# amplifier.net
KiCad netlist of a schematic drawn in Altium Designer
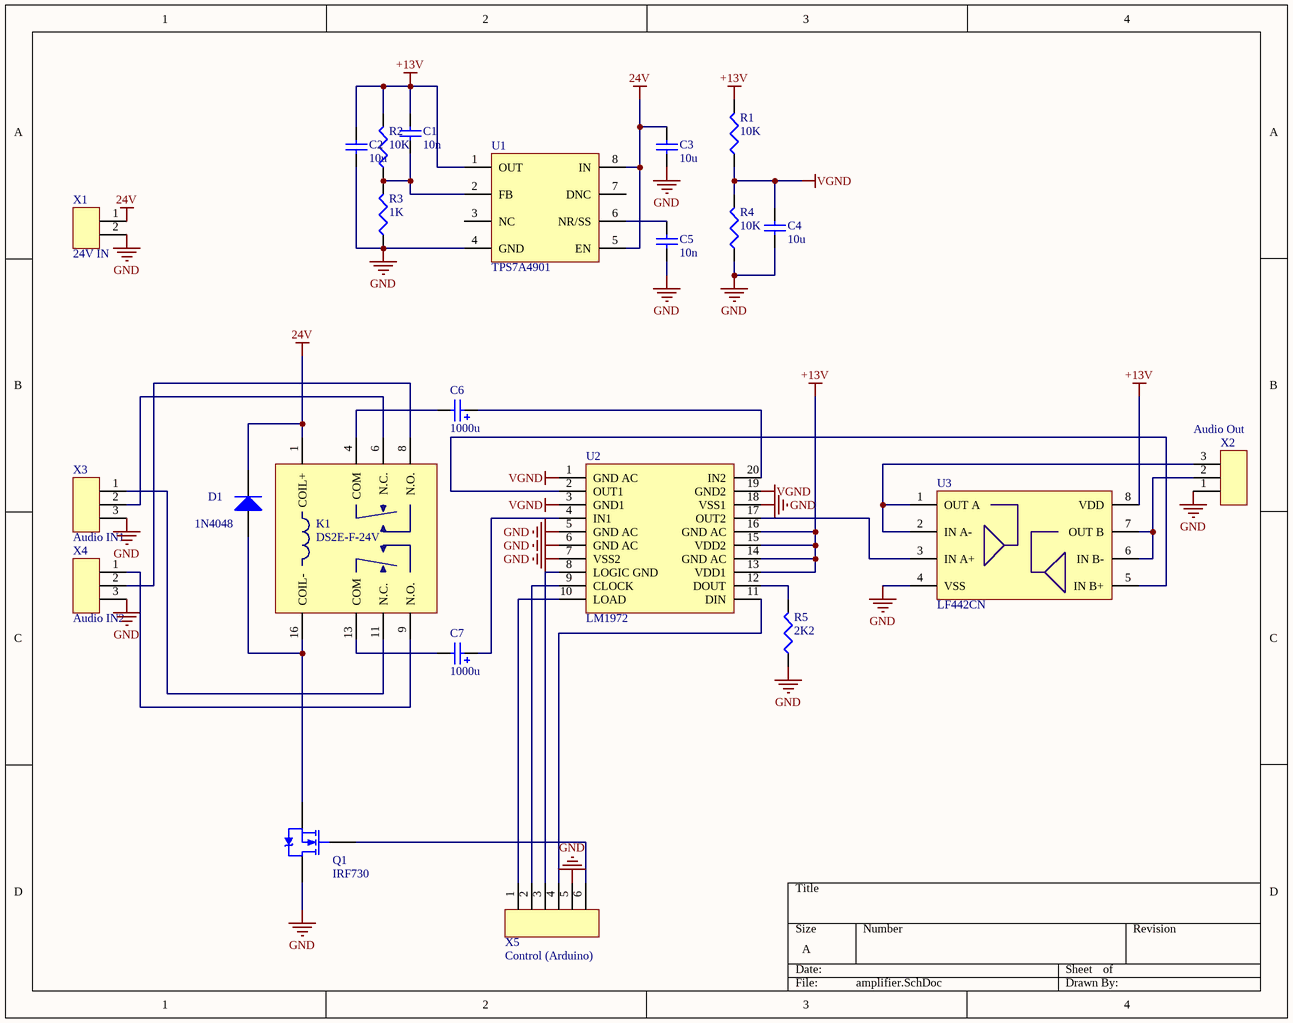
[diagram p0: amplifier.SchDoc]

(export (version "E")
  (design (tool "Eeschema 10.0.6"))
  (components
    (comp (ref "C1")
      (value "10n")
      (footprint "CAPC3216X17N")
      (description "CAP CER 10NF 50V 10% X7R 1206")
      (fields
        (field (name "MANUFACTURER") "Yageo")
        (field (name "MANUFACTURER PART NUMBER") "CC1206KRX7R9BB103")
      )
      (libsource (lib "BaseLab") (part "C1206C103K"))
    )
    (comp (ref "C2")
      (value "10u")
      (footprint "CAPC3216X17N")
      (description "CAP CER 100NF 50V 10% X7R 1206")
      (fields
        (field (name "MANUFACTURER") "Kemet")
        (field (name "MANUFACTURER PART NUMBER") "C1206C104K5RACTU")
      )
      (libsource (lib "BaseLab") (part "C1206C104K"))
    )
    (comp (ref "C3")
      (value "10u")
      (footprint "CAPC3216X17N")
      (description "CAP CER 100NF 50V 10% X7R 1206")
      (fields
        (field (name "MANUFACTURER") "Kemet")
        (field (name "MANUFACTURER PART NUMBER") "C1206C104K5RACTU")
      )
      (libsource (lib "BaseLab") (part "C1206C104K"))
    )
    (comp (ref "C4")
      (value "10u")
      (footprint "CAPC3216X17N")
      (description "CAP CER 100NF 50V 10% X7R 1206")
      (fields
        (field (name "MANUFACTURER") "Kemet")
        (field (name "MANUFACTURER PART NUMBER") "C1206C104K5RACTU")
      )
      (libsource (lib "BaseLab") (part "C1206C104K"))
    )
    (comp (ref "C5")
      (value "10n")
      (footprint "CAPC3216X17N")
      (description "CAP CER 10NF 50V 10% X7R 1206")
      (fields
        (field (name "MANUFACTURER") "Yageo")
        (field (name "MANUFACTURER PART NUMBER") "CC1206KRX7R9BB103")
      )
      (libsource (lib "BaseLab") (part "C1206C103K"))
    )
    (comp (ref "C6")
      (value "1000u")
      (footprint "Radial_0254_0381X0900")
      (description "CAP ALUM 1000UF 16V 20% RADIAL")
      (fields
        (field (name "MANUFACTURER") "Panasonic Electronic Components")
        (field (name "MANUFACTURER PART NUMBER") "ECA-1CM102B")
      )
      (libsource (lib "BaseLab") (part "CA-1CM102"))
    )
    (comp (ref "C7")
      (value "1000u")
      (footprint "Radial_0254_0381X0900")
      (description "CAP ALUM 1000UF 16V 20% RADIAL")
      (fields
        (field (name "MANUFACTURER") "Panasonic Electronic Components")
        (field (name "MANUFACTURER PART NUMBER") "ECA-1CM102B")
      )
      (libsource (lib "BaseLab") (part "CA-1CM102"))
    )
    (comp (ref "D1")
      (value "1N4048")
      (footprint "DO-35")
      (description "275 Amp Avg Power Silicon Rectifier Diode")
      (fields (field (name "PUBLISHER") "Altium Limited"))
      (libsource (lib "IR Rectifier - Standard Recovery") (part "1N4048"))
    )
    (comp (ref "K1")
      (value "DS2E-F-24V")
      (footprint "DS2E-F-DC24V")
      (description "Relay 24V")
      (fields
        (field (name "MANUFACTURER") "Panasonic Electric Works")
        (field (name "MANUFACTURER PART NUMBER") "DS2E-S-DC24V")
      )
      (libsource (lib "BaseLab") (part "DS2E-F-DC24V"))
    )
    (comp (ref "Q1")
      (value "IRF730")
      (footprint "TO-220AB")
      (description "HEXFET N-Channel Power MOSFET")
      (fields (field (name "PUBLISHER") "Altium Limited"))
      (libsource (lib "IR Discrete MOSFET - Power") (part "IRF730"))
    )
    (comp (ref "R1")
      (value "10K")
      (footprint "RESC2012X06M")
      (description "RES 10K OHM 1/8W 1% 0805 SMD")
      (fields
        (field (name "MANUFACTURER") "Yageo")
        (field (name "MANUFACTURER PART NUMBER") "RC0805FR-0710KL")
      )
      (libsource (lib "BaseLab") (part "RC0805FR-0710KL"))
    )
    (comp (ref "R2")
      (value "10K")
      (footprint "RESC2012X06M")
      (description "RES 10K OHM 1/8W 1% 0805 SMD")
      (fields
        (field (name "MANUFACTURER") "Yageo")
        (field (name "MANUFACTURER PART NUMBER") "RC0805FR-0710KL")
      )
      (libsource (lib "BaseLab") (part "RC0805FR-0710KL"))
    )
    (comp (ref "R3")
      (value "1K")
      (footprint "RESC3216X07N")
      (description "RES 1.00K OHM 1/4W 1% 1206 SMD")
      (fields
        (field (name "MANUFACTURER") "Yageo")
        (field (name "MANUFACTURER PART NUMBER") "RC1206FR-071KL")
      )
      (libsource (lib "BaseLab") (part "RC1206FR-071KL"))
    )
    (comp (ref "R4")
      (value "10K")
      (footprint "RESC2012X06M")
      (description "RES 10K OHM 1/8W 1% 0805 SMD")
      (fields
        (field (name "MANUFACTURER") "Yageo")
        (field (name "MANUFACTURER PART NUMBER") "RC0805FR-0710KL")
      )
      (libsource (lib "BaseLab") (part "RC0805FR-0710KL"))
    )
    (comp (ref "R5")
      (value "2K2")
      (footprint "RESC2012X06N")
      (description "RES 2.20K OHM 1/8W 1% 0805 SMD")
      (fields
        (field (name "MANUFACTURER") "Yageo")
        (field (name "MANUFACTURER PART NUMBER") "RC0805FR-072K2L")
      )
      (libsource (lib "BaseLab") (part "RC0805FR-072K2L"))
    )
    (comp (ref "U1")
      (value "TPS7A4901")
      (footprint "MSOP-8")
      (description "IC, ADJ LDO REG, 1.2V-33V, 0.15A, MSOP-8")
      (fields
        (field (name "MANUFACTURER") "Texas Instruments")
        (field (name "MANUFACTURER PART NUMBER") "TPS7A4901DGNR")
      )
      (libsource (lib "BaseLab") (part "TPS7A4901"))
    )
    (comp (ref "U2")
      (value "LM1972")
      (footprint "SOIC-20_0127_7.5mm")
      (libsource (lib "BaseLab") (part "LM1972"))
    )
    (comp (ref "U3")
      (value "LF442CN")
      (footprint "DIP-08_0254_0762_0420")
      (description "LF442 Dual Low Power JFET Input Operational Amplifier")
      (fields (field (name "MANUFACTURER") "TEXAS INSTRUMENTS"))
      (libsource (lib "BaseLab") (part "LF442CN"))
    )
    (comp (ref "X1")
      (value "24V IN")
      (footprint "CON_1X02S_0254")
      (description "Stecker 2-Pin")
      (fields
        (field (name "MANUFACTURER") "Sullins Connector Solutions")
        (field (name "MANUFACTURER PART NUMBER") "PREC040SFAN-RC")
      )
      (libsource (lib "BaseLab") (part "HDR1x02"))
    )
    (comp (ref "X2")
      (value "Audio Out")
      (footprint "CON_1X03S_0254")
      (description "Stecker 3-Pin")
      (fields
        (field (name "MANUFACTURER") "Sullins Connector Solutions")
        (field (name "MANUFACTURER PART NUMBER") "PREC040SFAN-RC")
      )
      (libsource (lib "BaseLab") (part "HDR1x03"))
    )
    (comp (ref "X3")
      (value "Audio IN1")
      (footprint "CON_1X03S_0254")
      (description "Stecker 3-Pin")
      (fields
        (field (name "MANUFACTURER") "Sullins Connector Solutions")
        (field (name "MANUFACTURER PART NUMBER") "PREC040SFAN-RC")
      )
      (libsource (lib "") (part "HDR1x03_1"))
    )
    (comp (ref "X4")
      (value "Audio IN2")
      (footprint "CON_1X03S_0254")
      (description "Stecker 3-Pin")
      (fields
        (field (name "MANUFACTURER") "Sullins Connector Solutions")
        (field (name "MANUFACTURER PART NUMBER") "PREC040SFAN-RC")
      )
      (libsource (lib "") (part "HDR1x03_1"))
    )
    (comp (ref "X5")
      (value "Control (Arduino)")
      (footprint "CON_1X06S_0254")
      (description "Stecker 4-Pin")
      (fields
        (field (name "MANUFACTURER") "Sullins Connector Solutions")
        (field (name "MANUFACTURER PART NUMBER") "PREC040SFAN-RC")
      )
      (libsource (lib "BaseLab") (part "HDR1x06"))
    )
  )
  (nets
    (net (code "1") (name "+13V") (class "Default")
      (node (ref "C1") (pin "2") (pinfunction "2_2") (pintype "passive"))
      (node (ref "C2") (pin "2") (pinfunction "2_2") (pintype "passive"))
      (node (ref "R1") (pin "2") (pinfunction "2_2") (pintype "passive"))
      (node (ref "R2") (pin "2") (pinfunction "2_2") (pintype "passive"))
      (node (ref "U1") (pin "1") (pinfunction "OUT_1") (pintype "passive"))
      (node (ref "U2") (pin "13") (pinfunction "VDD1_13") (pintype "passive"))
      (node (ref "U2") (pin "14") (pinfunction "GND_AC_14") (pintype "passive"))
      (node (ref "U2") (pin "15") (pinfunction "VDD2_15") (pintype "passive"))
      (node (ref "U2") (pin "16") (pinfunction "GND_AC_16") (pintype "passive"))
      (node (ref "U3") (pin "8") (pinfunction "VDD_8") (pintype "passive"))
    )
    (net (code "2") (name "24V") (class "Default")
      (node (ref "C3") (pin "2") (pinfunction "2_2") (pintype "passive"))
      (node (ref "D1") (pin "2") (pinfunction "K_2") (pintype "passive"))
      (node (ref "K1") (pin "1") (pinfunction "COIL+_1") (pintype "passive"))
      (node (ref "U1") (pin "5") (pinfunction "EN_5") (pintype "passive"))
      (node (ref "U1") (pin "8") (pinfunction "IN_8") (pintype "passive"))
      (node (ref "X1") (pin "1") (pinfunction "1_1") (pintype "passive"))
    )
    (net (code "3") (name "GND") (class "Default")
      (node (ref "C2") (pin "1") (pinfunction "1_1") (pintype "passive"))
      (node (ref "C3") (pin "1") (pinfunction "1_1") (pintype "passive"))
      (node (ref "C4") (pin "1") (pinfunction "1_1") (pintype "passive"))
      (node (ref "C5") (pin "1") (pinfunction "1_1") (pintype "passive"))
      (node (ref "Q1") (pin "2") (pinfunction "D_2") (pintype "passive"))
      (node (ref "R3") (pin "1") (pinfunction "1_1") (pintype "passive"))
      (node (ref "R4") (pin "1") (pinfunction "1_1") (pintype "passive"))
      (node (ref "R5") (pin "1") (pinfunction "1_1") (pintype "passive"))
      (node (ref "U1") (pin "4") (pinfunction "GND_4") (pintype "passive"))
      (node (ref "U2") (pin "18") (pinfunction "VSS1_18") (pintype "passive"))
      (node (ref "U2") (pin "5") (pinfunction "GND_AC_5") (pintype "passive"))
      (node (ref "U2") (pin "6") (pinfunction "GND_AC_6") (pintype "passive"))
      (node (ref "U2") (pin "7") (pinfunction "VSS2_7") (pintype "passive"))
      (node (ref "U3") (pin "4") (pinfunction "VSS_4") (pintype "passive"))
      (node (ref "X1") (pin "2") (pinfunction "2_2") (pintype "passive"))
      (node (ref "X2") (pin "1") (pinfunction "1_1") (pintype "passive"))
      (node (ref "X3") (pin "3") (pinfunction "3_3") (pintype "passive"))
      (node (ref "X4") (pin "3") (pinfunction "3_3") (pintype "passive"))
      (node (ref "X5") (pin "5") (pinfunction "5_5") (pintype "passive"))
    )
    (net (code "4") (name "Net-(C6-Pad2)") (class "Default")
      (node (ref "C6") (pin "2") (pinfunction "2_2") (pintype "passive"))
      (node (ref "K1") (pin "4") (pinfunction "COM_4") (pintype "passive"))
    )
    (net (code "5") (name "Net-(C7-Pad2)") (class "Default")
      (node (ref "C7") (pin "2") (pinfunction "2_2") (pintype "passive"))
      (node (ref "K1") (pin "13") (pinfunction "COM_13") (pintype "passive"))
    )
    (net (code "6") (name "Net-(D1-A)") (class "Default")
      (node (ref "D1") (pin "1") (pinfunction "A_1") (pintype "passive"))
      (node (ref "K1") (pin "16") (pinfunction "COIL-_16") (pintype "passive"))
      (node (ref "Q1") (pin "3") (pinfunction "S_3") (pintype "passive"))
    )
    (net (code "7") (name "Net-(K1-N.C.-Pad6)") (class "Default")
      (node (ref "K1") (pin "6") (pinfunction "N.C._6") (pintype "passive"))
      (node (ref "X3") (pin "2") (pinfunction "2_2") (pintype "passive"))
    )
    (net (code "8") (name "Net-(K1-N.C.-Pad11)") (class "Default")
      (node (ref "K1") (pin "11") (pinfunction "N.C._11") (pintype "passive"))
      (node (ref "X3") (pin "1") (pinfunction "1_1") (pintype "passive"))
    )
    (net (code "9") (name "Net-(K1-N.O.-Pad8)") (class "Default")
      (node (ref "K1") (pin "8") (pinfunction "N.O._8") (pintype "passive"))
      (node (ref "X4") (pin "2") (pinfunction "2_2") (pintype "passive"))
    )
    (net (code "10") (name "Net-(K1-N.O.-Pad9)") (class "Default")
      (node (ref "K1") (pin "9") (pinfunction "N.O._9") (pintype "passive"))
      (node (ref "X4") (pin "1") (pinfunction "1_1") (pintype "passive"))
    )
    (net (code "11") (name "Net-(Q1-G)") (class "Default")
      (node (ref "Q1") (pin "1") (pinfunction "G_1") (pintype "passive"))
      (node (ref "X5") (pin "6") (pinfunction "6_6") (pintype "passive"))
    )
    (net (code "12") (name "Net-(U1-FB)") (class "Default")
      (node (ref "C1") (pin "1") (pinfunction "1_1") (pintype "passive"))
      (node (ref "R2") (pin "1") (pinfunction "1_1") (pintype "passive"))
      (node (ref "R3") (pin "2") (pinfunction "2_2") (pintype "passive"))
      (node (ref "U1") (pin "2") (pinfunction "FB_2") (pintype "passive"))
    )
    (net (code "13") (name "Net-(U1-NR{slash}SS)") (class "Default")
      (node (ref "C5") (pin "2") (pinfunction "2_2") (pintype "passive"))
      (node (ref "U1") (pin "6") (pinfunction "NR/SS_6") (pintype "passive"))
    )
    (net (code "14") (name "Net-(U2-CLOCK)") (class "Default")
      (node (ref "U2") (pin "9") (pinfunction "CLOCK_9") (pintype "passive"))
      (node (ref "X5") (pin "2") (pinfunction "2_2") (pintype "passive"))
    )
    (net (code "15") (name "Net-(U2-DIN)") (class "Default")
      (node (ref "U2") (pin "11") (pinfunction "DIN_11") (pintype "passive"))
      (node (ref "X5") (pin "4") (pinfunction "4_4") (pintype "passive"))
    )
    (net (code "16") (name "Net-(U2-DOUT)") (class "Default")
      (node (ref "R5") (pin "2") (pinfunction "2_2") (pintype "passive"))
      (node (ref "U2") (pin "12") (pinfunction "DOUT_12") (pintype "passive"))
    )
    (net (code "17") (name "Net-(U2-IN1)") (class "Default")
      (node (ref "C7") (pin "1") (pinfunction "1_1") (pintype "passive"))
      (node (ref "U2") (pin "4") (pinfunction "IN1_4") (pintype "passive"))
    )
    (net (code "18") (name "Net-(U2-IN2)") (class "Default")
      (node (ref "C6") (pin "1") (pinfunction "1_1") (pintype "passive"))
      (node (ref "U2") (pin "20") (pinfunction "IN2_20") (pintype "passive"))
    )
    (net (code "19") (name "Net-(U2-LOAD)") (class "Default")
      (node (ref "U2") (pin "10") (pinfunction "LOAD_10") (pintype "passive"))
      (node (ref "X5") (pin "1") (pinfunction "1_1") (pintype "passive"))
    )
    (net (code "20") (name "Net-(U2-LOGIC_GND)") (class "Default")
      (node (ref "U2") (pin "8") (pinfunction "LOGIC_GND_8") (pintype "passive"))
      (node (ref "X5") (pin "3") (pinfunction "3_3") (pintype "passive"))
    )
    (net (code "21") (name "Net-(U2-OUT1)") (class "Default")
      (node (ref "U2") (pin "2") (pinfunction "OUT1_2") (pintype "passive"))
      (node (ref "U3") (pin "5") (pinfunction "IN_B+_5") (pintype "passive"))
    )
    (net (code "22") (name "Net-(U2-OUT2)") (class "Default")
      (node (ref "U2") (pin "17") (pinfunction "OUT2_17") (pintype "passive"))
      (node (ref "U3") (pin "3") (pinfunction "IN_A+_3") (pintype "passive"))
    )
    (net (code "23") (name "Net-(U3-IN_A-)") (class "Default")
      (node (ref "U3") (pin "1") (pinfunction "OUT_A_1") (pintype "passive"))
      (node (ref "U3") (pin "2") (pinfunction "IN_A-_2") (pintype "passive"))
      (node (ref "X2") (pin "3") (pinfunction "3_3") (pintype "passive"))
    )
    (net (code "24") (name "Net-(U3-IN_B-)") (class "Default")
      (node (ref "U3") (pin "6") (pinfunction "IN_B-_6") (pintype "passive"))
      (node (ref "U3") (pin "7") (pinfunction "OUT_B_7") (pintype "passive"))
      (node (ref "X2") (pin "2") (pinfunction "2_2") (pintype "passive"))
    )
    (net (code "25") (name "VGND") (class "Default")
      (node (ref "C4") (pin "2") (pinfunction "2_2") (pintype "passive"))
      (node (ref "R1") (pin "1") (pinfunction "1_1") (pintype "passive"))
      (node (ref "R4") (pin "2") (pinfunction "2_2") (pintype "passive"))
      (node (ref "U2") (pin "1") (pinfunction "GND_AC_1") (pintype "passive"))
      (node (ref "U2") (pin "19") (pinfunction "GND2_19") (pintype "passive"))
      (node (ref "U2") (pin "3") (pinfunction "GND1_3") (pintype "passive"))
    )
    (net (code "26") (name "unconnected-(U1-DNC-Pad7)") (class "Default")
      (node (ref "U1") (pin "7") (pinfunction "DNC_7") (pintype "passive"))
    )
    (net (code "27") (name "unconnected-(U1-NC-Pad3)") (class "Default")
      (node (ref "U1") (pin "3") (pinfunction "NC_3") (pintype "passive"))
    )
  )
)
